# 005_DP.net
KiCad netlist of a schematic drawn in Altium Designer
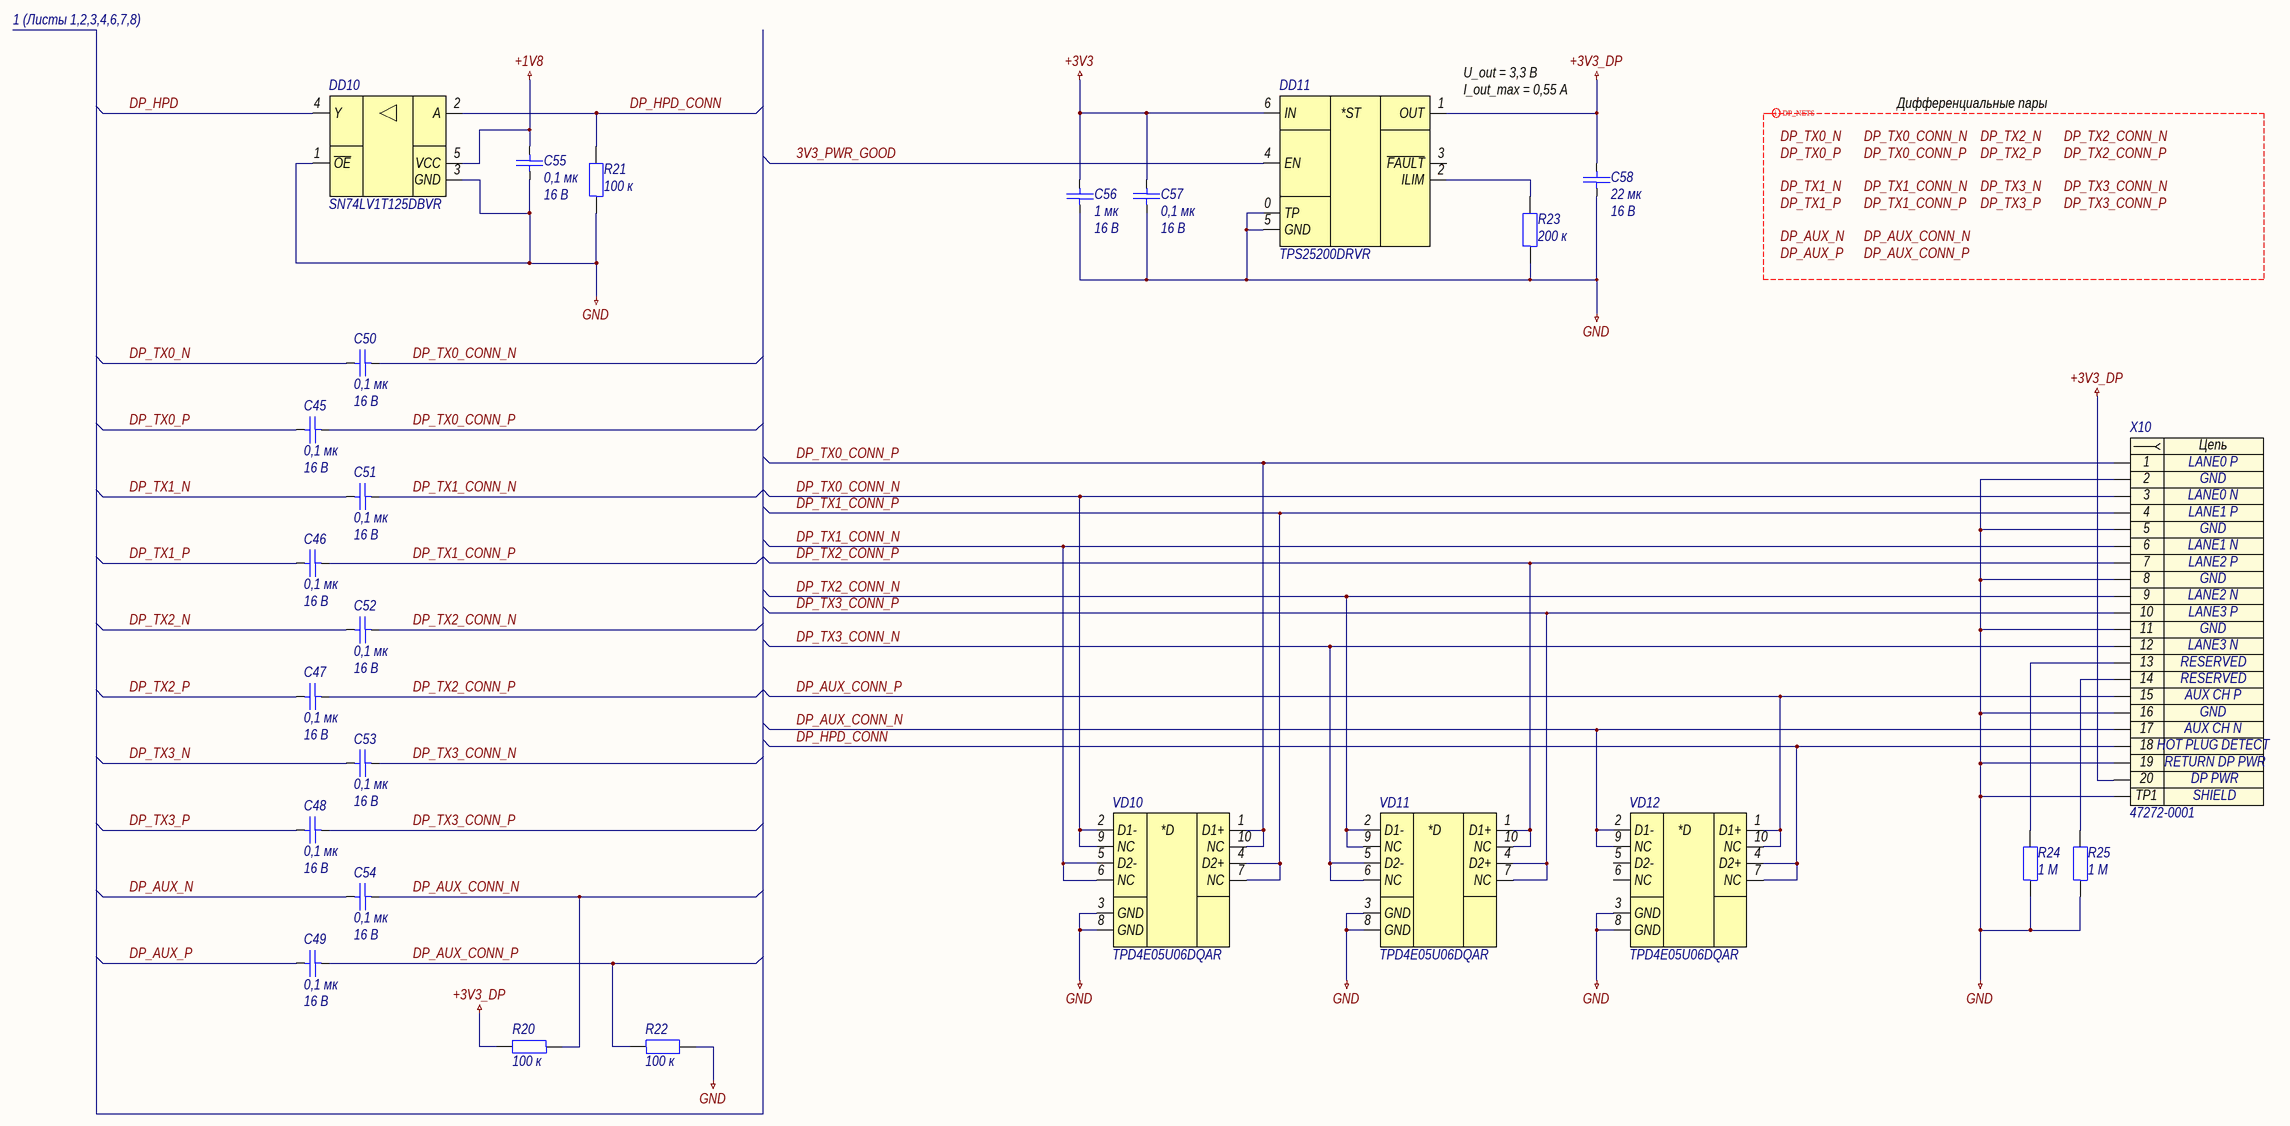
[diagram p0: 005_DP.SchDoc]

(export (version "E")
  (design (tool "Eeschema 10.0.6"))
  (components
    (comp (ref "C45")
      (value "0,1 мк")
      (footprint "C0603")
      (description "=Описание")
      (fields (field (name "НАПРЯЖЕНИЕ") "16 В"))
      (libsource (lib "Database_Students") (part "CAPACITOR-NONPOLAR"))
    )
    (comp (ref "C46")
      (value "0,1 мк")
      (footprint "C0603")
      (description "=Описание")
      (fields (field (name "НАПРЯЖЕНИЕ") "16 В"))
      (libsource (lib "Database_Students") (part "CAPACITOR-NONPOLAR"))
    )
    (comp (ref "C47")
      (value "0,1 мк")
      (footprint "C0603")
      (description "=Описание")
      (fields (field (name "НАПРЯЖЕНИЕ") "16 В"))
      (libsource (lib "Database_Students") (part "CAPACITOR-NONPOLAR"))
    )
    (comp (ref "C48")
      (value "0,1 мк")
      (footprint "C0603")
      (description "=Описание")
      (fields (field (name "НАПРЯЖЕНИЕ") "16 В"))
      (libsource (lib "Database_Students") (part "CAPACITOR-NONPOLAR"))
    )
    (comp (ref "C49")
      (value "0,1 мк")
      (footprint "C0603")
      (description "=Описание")
      (fields (field (name "НАПРЯЖЕНИЕ") "16 В"))
      (libsource (lib "Database_Students") (part "CAPACITOR-NONPOLAR"))
    )
    (comp (ref "C50")
      (value "0,1 мк")
      (footprint "C0603")
      (description "=Описание")
      (fields (field (name "НАПРЯЖЕНИЕ") "16 В"))
      (libsource (lib "Database_Students") (part "CAPACITOR-NONPOLAR"))
    )
    (comp (ref "C51")
      (value "0,1 мк")
      (footprint "C0603")
      (description "=Описание")
      (fields (field (name "НАПРЯЖЕНИЕ") "16 В"))
      (libsource (lib "Database_Students") (part "CAPACITOR-NONPOLAR"))
    )
    (comp (ref "C52")
      (value "0,1 мк")
      (footprint "C0603")
      (description "=Описание")
      (fields (field (name "НАПРЯЖЕНИЕ") "16 В"))
      (libsource (lib "Database_Students") (part "CAPACITOR-NONPOLAR"))
    )
    (comp (ref "C53")
      (value "0,1 мк")
      (footprint "C0603")
      (description "=Описание")
      (fields (field (name "НАПРЯЖЕНИЕ") "16 В"))
      (libsource (lib "Database_Students") (part "CAPACITOR-NONPOLAR"))
    )
    (comp (ref "C54")
      (value "0,1 мк")
      (footprint "C0603")
      (description "=Описание")
      (fields (field (name "НАПРЯЖЕНИЕ") "16 В"))
      (libsource (lib "Database_Students") (part "CAPACITOR-NONPOLAR"))
    )
    (comp (ref "C55")
      (value "0,1 мк")
      (footprint "C0603")
      (description "=Описание")
      (fields (field (name "НАПРЯЖЕНИЕ") "16 В"))
      (libsource (lib "Database_Students") (part "CAPACITOR-NONPOLAR"))
    )
    (comp (ref "C56")
      (value "1 мк")
      (footprint "C0603")
      (description "=Описание")
      (fields (field (name "НАПРЯЖЕНИЕ") "16 В"))
      (libsource (lib "Database_Students") (part "CAPACITOR-NONPOLAR"))
    )
    (comp (ref "C57")
      (value "0,1 мк")
      (footprint "C0603")
      (description "=Описание")
      (fields (field (name "НАПРЯЖЕНИЕ") "16 В"))
      (libsource (lib "Database_Students") (part "CAPACITOR-NONPOLAR"))
    )
    (comp (ref "C58")
      (value "22 мк")
      (footprint "C0805")
      (description "=Описание")
      (fields (field (name "НАПРЯЖЕНИЕ") "16 В"))
      (libsource (lib "Database_Students") (part "CAPACITOR-NONPOLAR"))
    )
    (comp (ref "DD10")
      (value "SN74LV1T125DBVR")
      (footprint "SOT-23-5-P95-290X280X145")
      (description "=Описание")
      (libsource (lib "Database_Students") (part "SN74LV1T125DBVR"))
    )
    (comp (ref "DD11")
      (value "TPS25200DRVR")
      (footprint "WSON-6-P65-200X200X80-L30X25-T170X110")
      (description "=Описание")
      (libsource (lib "Database_Students") (part "TPS25200DRVR"))
    )
    (comp (ref "R20")
      (value "100 к")
      (footprint "R0603")
      (description "=Описание")
      (libsource (lib "Database_Students") (part "RESISTOR-COMMON"))
    )
    (comp (ref "R21")
      (value "100 к")
      (footprint "R0603")
      (description "=Описание")
      (libsource (lib "Database_Students") (part "RESISTOR-COMMON"))
    )
    (comp (ref "R22")
      (value "100 к")
      (footprint "R0603")
      (description "=Описание")
      (libsource (lib "Database_Students") (part "RESISTOR-COMMON"))
    )
    (comp (ref "R23")
      (value "200 к")
      (footprint "R0603")
      (description "=Описание")
      (libsource (lib "Database_Students") (part "RESISTOR-COMMON"))
    )
    (comp (ref "R24")
      (value "1 М")
      (footprint "R0603")
      (description "=Описание")
      (libsource (lib "Database_Students") (part "RESISTOR-COMMON"))
    )
    (comp (ref "R25")
      (value "1 М")
      (footprint "R0603")
      (description "=Описание")
      (libsource (lib "Database_Students") (part "RESISTOR-COMMON"))
    )
    (comp (ref "VD10")
      (value "TPD4E05U06DQAR")
      (footprint "USON-10-P50-250X100X55-L36X20")
      (description "=Описание")
      (libsource (lib "Database_Students") (part "TPD4E05U06DQAR"))
    )
    (comp (ref "VD11")
      (value "TPD4E05U06DQAR")
      (footprint "USON-10-P50-250X100X55-L36X20")
      (description "=Описание")
      (libsource (lib "Database_Students") (part "TPD4E05U06DQAR"))
    )
    (comp (ref "VD12")
      (value "TPD4E05U06DQAR")
      (footprint "USON-10-P50-250X100X55-L36X20")
      (description "=Описание")
      (libsource (lib "Database_Students") (part "TPD4E05U06DQAR"))
    )
    (comp (ref "X10")
      (value "47272-0001")
      (footprint "47272-0001")
      (description "=Описание")
      (libsource (lib "Database_Students") (part "HEADER-20-TP1-SCT"))
    )
  )
  (nets
    (net (code "1") (name "+1V8") (class "Default")
      (node (ref "C55") (pin "2") (pinfunction "2_2") (pintype "passive"))
      (node (ref "DD10") (pin "5") (pinfunction "VCC_5") (pintype "passive"))
    )
    (net (code "2") (name "+3V3") (class "Default")
      (node (ref "C56") (pin "1") (pinfunction "1_1") (pintype "passive"))
      (node (ref "C57") (pin "2") (pinfunction "2_2") (pintype "passive"))
      (node (ref "DD11") (pin "6") (pinfunction "IN_6") (pintype "passive"))
    )
    (net (code "3") (name "+3V3_DP") (class "Default")
      (node (ref "C58") (pin "1") (pinfunction "1_1") (pintype "passive"))
      (node (ref "DD11") (pin "1") (pinfunction "OUT_1") (pintype "passive"))
      (node (ref "R20") (pin "2") (pinfunction "2_2") (pintype "passive"))
      (node (ref "X10") (pin "20") (pinfunction "20_20") (pintype "passive"))
    )
    (net (code "4") (name "/3V3_PWR_GOOD") (class "Default")
      (node (ref "DD11") (pin "4") (pinfunction "EN_4") (pintype "passive"))
    )
    (net (code "5") (name "/DP_AUX_CONN_N") (class "Default")
      (node (ref "C54") (pin "2") (pinfunction "2_2") (pintype "passive"))
      (node (ref "R20") (pin "1") (pinfunction "1_1") (pintype "passive"))
      (node (ref "VD12") (pin "2") (pinfunction "D1-_2") (pintype "passive"))
      (node (ref "VD12") (pin "9") (pinfunction "NC_9") (pintype "passive"))
      (node (ref "X10") (pin "17") (pinfunction "17_17") (pintype "passive"))
    )
    (net (code "6") (name "/DP_AUX_CONN_P") (class "Default")
      (node (ref "C49") (pin "2") (pinfunction "2_2") (pintype "passive"))
      (node (ref "R22") (pin "1") (pinfunction "1_1") (pintype "passive"))
      (node (ref "VD12") (pin "1") (pinfunction "D1+_1") (pintype "passive"))
      (node (ref "VD12") (pin "10") (pinfunction "NC_10") (pintype "passive"))
      (node (ref "X10") (pin "15") (pinfunction "15_15") (pintype "passive"))
    )
    (net (code "7") (name "/DP_AUX_N") (class "Default")
      (node (ref "C54") (pin "1") (pinfunction "1_1") (pintype "passive"))
    )
    (net (code "8") (name "/DP_AUX_P") (class "Default")
      (node (ref "C49") (pin "1") (pinfunction "1_1") (pintype "passive"))
    )
    (net (code "9") (name "/DP_HPD") (class "Default")
      (node (ref "DD10") (pin "4") (pinfunction "Y_4") (pintype "passive"))
    )
    (net (code "10") (name "/DP_HPD_CONN") (class "Default")
      (node (ref "DD10") (pin "2") (pinfunction "A_2") (pintype "passive"))
      (node (ref "R21") (pin "2") (pinfunction "2_2") (pintype "passive"))
      (node (ref "VD12") (pin "4") (pinfunction "D2+_4") (pintype "passive"))
      (node (ref "VD12") (pin "7") (pinfunction "NC_7") (pintype "passive"))
      (node (ref "X10") (pin "18") (pinfunction "18_18") (pintype "passive"))
    )
    (net (code "11") (name "/DP_TX0_CONN_N") (class "Default")
      (node (ref "C50") (pin "2") (pinfunction "2_2") (pintype "passive"))
      (node (ref "VD10") (pin "2") (pinfunction "D1-_2") (pintype "passive"))
      (node (ref "VD10") (pin "9") (pinfunction "NC_9") (pintype "passive"))
      (node (ref "X10") (pin "3") (pinfunction "3_3") (pintype "passive"))
    )
    (net (code "12") (name "/DP_TX0_CONN_P") (class "Default")
      (node (ref "C45") (pin "2") (pinfunction "2_2") (pintype "passive"))
      (node (ref "VD10") (pin "1") (pinfunction "D1+_1") (pintype "passive"))
      (node (ref "VD10") (pin "10") (pinfunction "NC_10") (pintype "passive"))
      (node (ref "X10") (pin "1") (pinfunction "1_1") (pintype "passive"))
    )
    (net (code "13") (name "/DP_TX0_N") (class "Default")
      (node (ref "C50") (pin "1") (pinfunction "1_1") (pintype "passive"))
    )
    (net (code "14") (name "/DP_TX0_P") (class "Default")
      (node (ref "C45") (pin "1") (pinfunction "1_1") (pintype "passive"))
    )
    (net (code "15") (name "/DP_TX1_CONN_N") (class "Default")
      (node (ref "C51") (pin "2") (pinfunction "2_2") (pintype "passive"))
      (node (ref "VD10") (pin "5") (pinfunction "D2-_5") (pintype "passive"))
      (node (ref "VD10") (pin "6") (pinfunction "NC_6") (pintype "passive"))
      (node (ref "X10") (pin "6") (pinfunction "6_6") (pintype "passive"))
    )
    (net (code "16") (name "/DP_TX1_CONN_P") (class "Default")
      (node (ref "C46") (pin "2") (pinfunction "2_2") (pintype "passive"))
      (node (ref "VD10") (pin "4") (pinfunction "D2+_4") (pintype "passive"))
      (node (ref "VD10") (pin "7") (pinfunction "NC_7") (pintype "passive"))
      (node (ref "X10") (pin "4") (pinfunction "4_4") (pintype "passive"))
    )
    (net (code "17") (name "/DP_TX1_N") (class "Default")
      (node (ref "C51") (pin "1") (pinfunction "1_1") (pintype "passive"))
    )
    (net (code "18") (name "/DP_TX1_P") (class "Default")
      (node (ref "C46") (pin "1") (pinfunction "1_1") (pintype "passive"))
    )
    (net (code "19") (name "/DP_TX2_CONN_N") (class "Default")
      (node (ref "C52") (pin "2") (pinfunction "2_2") (pintype "passive"))
      (node (ref "VD11") (pin "2") (pinfunction "D1-_2") (pintype "passive"))
      (node (ref "VD11") (pin "9") (pinfunction "NC_9") (pintype "passive"))
      (node (ref "X10") (pin "9") (pinfunction "9_9") (pintype "passive"))
    )
    (net (code "20") (name "/DP_TX2_CONN_P") (class "Default")
      (node (ref "C47") (pin "2") (pinfunction "2_2") (pintype "passive"))
      (node (ref "VD11") (pin "1") (pinfunction "D1+_1") (pintype "passive"))
      (node (ref "VD11") (pin "10") (pinfunction "NC_10") (pintype "passive"))
      (node (ref "X10") (pin "7") (pinfunction "7_7") (pintype "passive"))
    )
    (net (code "21") (name "/DP_TX2_N") (class "Default")
      (node (ref "C52") (pin "1") (pinfunction "1_1") (pintype "passive"))
    )
    (net (code "22") (name "/DP_TX2_P") (class "Default")
      (node (ref "C47") (pin "1") (pinfunction "1_1") (pintype "passive"))
    )
    (net (code "23") (name "/DP_TX3_CONN_N") (class "Default")
      (node (ref "C53") (pin "2") (pinfunction "2_2") (pintype "passive"))
      (node (ref "VD11") (pin "5") (pinfunction "D2-_5") (pintype "passive"))
      (node (ref "VD11") (pin "6") (pinfunction "NC_6") (pintype "passive"))
      (node (ref "X10") (pin "12") (pinfunction "12_12") (pintype "passive"))
    )
    (net (code "24") (name "/DP_TX3_CONN_P") (class "Default")
      (node (ref "C48") (pin "2") (pinfunction "2_2") (pintype "passive"))
      (node (ref "VD11") (pin "4") (pinfunction "D2+_4") (pintype "passive"))
      (node (ref "VD11") (pin "7") (pinfunction "NC_7") (pintype "passive"))
      (node (ref "X10") (pin "10") (pinfunction "10_10") (pintype "passive"))
    )
    (net (code "25") (name "/DP_TX3_N") (class "Default")
      (node (ref "C53") (pin "1") (pinfunction "1_1") (pintype "passive"))
    )
    (net (code "26") (name "/DP_TX3_P") (class "Default")
      (node (ref "C48") (pin "1") (pinfunction "1_1") (pintype "passive"))
    )
    (net (code "27") (name "GND") (class "Default")
      (node (ref "C55") (pin "1") (pinfunction "1_1") (pintype "passive"))
      (node (ref "C56") (pin "2") (pinfunction "2_2") (pintype "passive"))
      (node (ref "C57") (pin "1") (pinfunction "1_1") (pintype "passive"))
      (node (ref "C58") (pin "2") (pinfunction "2_2") (pintype "passive"))
      (node (ref "DD10") (pin "1") (pinfunction "~{OE}_1") (pintype "passive"))
      (node (ref "DD10") (pin "3") (pinfunction "GND_3") (pintype "passive"))
      (node (ref "DD11") (pin "0") (pinfunction "TP_0") (pintype "passive"))
      (node (ref "DD11") (pin "5") (pinfunction "GND_5") (pintype "passive"))
      (node (ref "R21") (pin "1") (pinfunction "1_1") (pintype "passive"))
      (node (ref "R22") (pin "2") (pinfunction "2_2") (pintype "passive"))
      (node (ref "R23") (pin "1") (pinfunction "1_1") (pintype "passive"))
      (node (ref "R24") (pin "1") (pinfunction "1_1") (pintype "passive"))
      (node (ref "R25") (pin "1") (pinfunction "1_1") (pintype "passive"))
      (node (ref "VD10") (pin "3") (pinfunction "GND_3") (pintype "passive"))
      (node (ref "VD10") (pin "8") (pinfunction "GND_8") (pintype "passive"))
      (node (ref "VD11") (pin "3") (pinfunction "GND_3") (pintype "passive"))
      (node (ref "VD11") (pin "8") (pinfunction "GND_8") (pintype "passive"))
      (node (ref "VD12") (pin "3") (pinfunction "GND_3") (pintype "passive"))
      (node (ref "VD12") (pin "8") (pinfunction "GND_8") (pintype "passive"))
      (node (ref "X10") (pin "11") (pinfunction "11_11") (pintype "passive"))
      (node (ref "X10") (pin "16") (pinfunction "16_16") (pintype "passive"))
      (node (ref "X10") (pin "19") (pinfunction "19_19") (pintype "passive"))
      (node (ref "X10") (pin "2") (pinfunction "2_2") (pintype "passive"))
      (node (ref "X10") (pin "5") (pinfunction "5_5") (pintype "passive"))
      (node (ref "X10") (pin "8") (pinfunction "8_8") (pintype "passive"))
      (node (ref "X10") (pin "TP1") (pinfunction "TP1_TP1") (pintype "passive"))
    )
    (net (code "28") (name "Net-(DD11-ILIM)") (class "Default")
      (node (ref "DD11") (pin "2") (pinfunction "ILIM_2") (pintype "passive"))
      (node (ref "R23") (pin "2") (pinfunction "2_2") (pintype "passive"))
    )
    (net (code "29") (name "Net-(R24-Pad2)") (class "Default")
      (node (ref "R24") (pin "2") (pinfunction "2_2") (pintype "passive"))
      (node (ref "X10") (pin "13") (pinfunction "13_13") (pintype "passive"))
    )
    (net (code "30") (name "Net-(R25-Pad2)") (class "Default")
      (node (ref "R25") (pin "2") (pinfunction "2_2") (pintype "passive"))
      (node (ref "X10") (pin "14") (pinfunction "14_14") (pintype "passive"))
    )
    (net (code "31") (name "unconnected-(DD11-~{FAULT}-Pad3)") (class "Default")
      (node (ref "DD11") (pin "3") (pinfunction "~{FAULT}_3") (pintype "passive"))
    )
    (net (code "32") (name "unconnected-(VD12-D2--Pad5)") (class "Default")
      (node (ref "VD12") (pin "5") (pinfunction "D2-_5") (pintype "passive"))
    )
    (net (code "33") (name "unconnected-(VD12-NC-Pad6)") (class "Default")
      (node (ref "VD12") (pin "6") (pinfunction "NC_6") (pintype "passive"))
    )
  )
)
